# MCU.net
KiCad netlist of a schematic drawn in Altium Designer
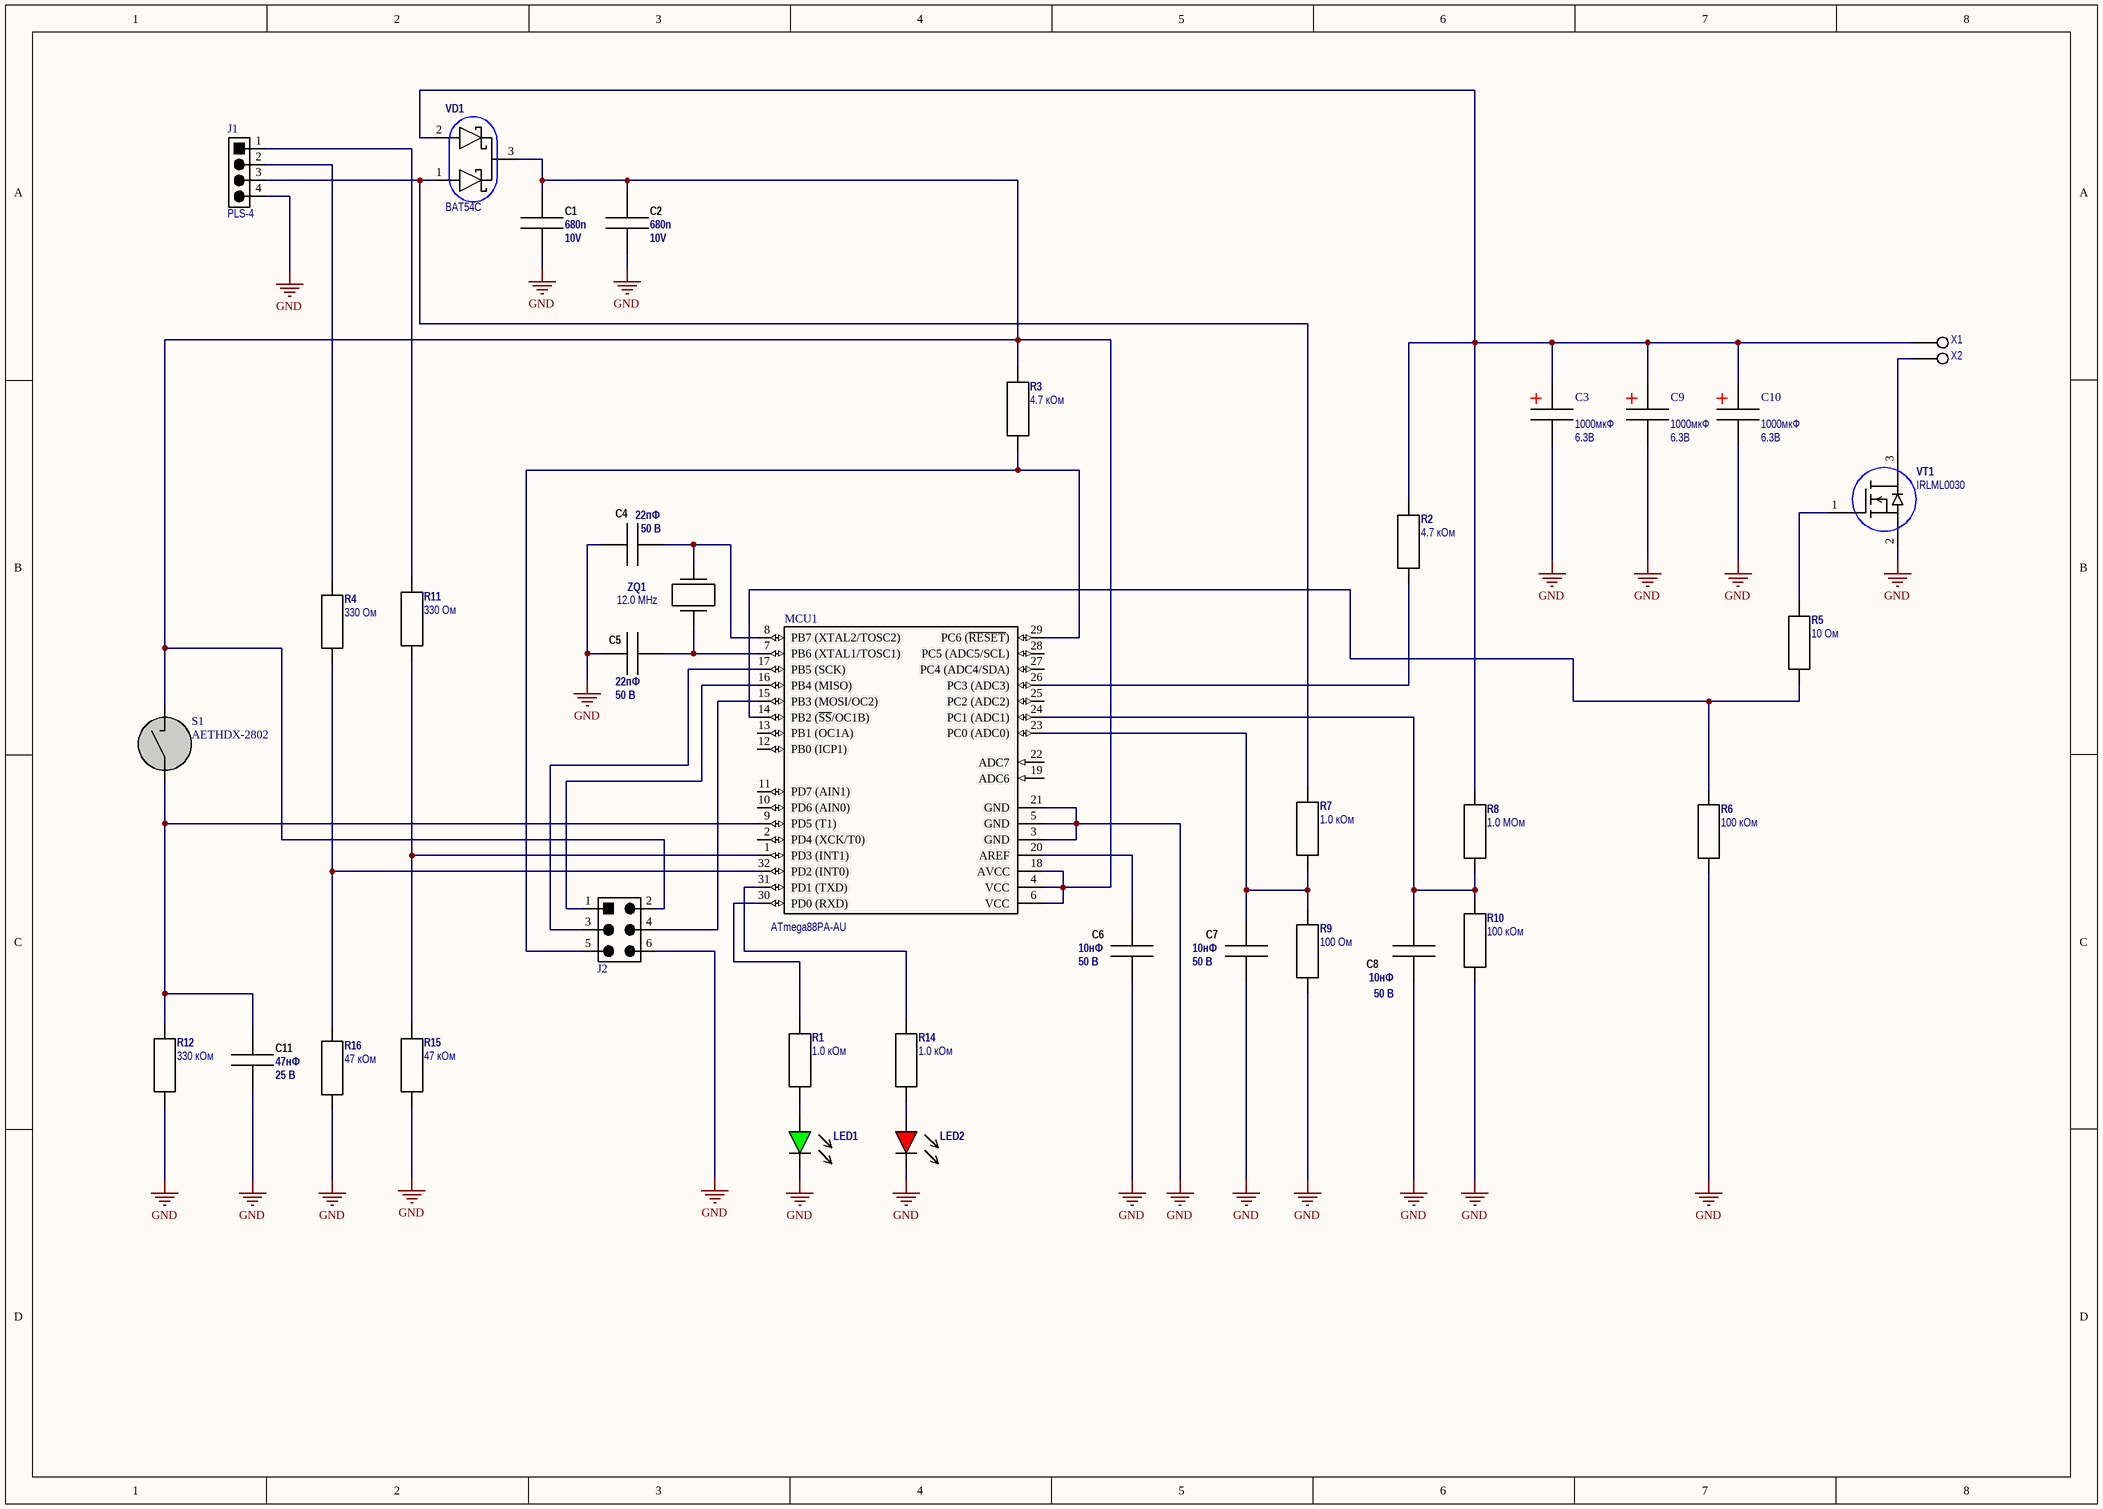
[diagram p0: MCU.SchDoc]

(export (version "E")
  (design (tool "Eeschema 10.0.6"))
  (components
    (comp (ref "C1")
      (value "680нФ 10 В 10% 0603 X7R")
      (footprint "C0603")
      (description "конденсатор керамический SMD")
      (fields
        (field (name "SHOWVALUE") "680n")
        (field (name "VOLTAGE") "10V")
        (field (name "PART NUMBER") "680нФ 10В")
      )
      (libsource (lib "Capacitors 0603 X7R") (part "47нФ 25 В"))
    )
    (comp (ref "C2")
      (value "680нФ 10 В 10% 0603 X7R")
      (footprint "C0603")
      (description "конденсатор керамический SMD")
      (fields
        (field (name "SHOWVALUE") "680n")
        (field (name "VOLTAGE") "10V")
        (field (name "PART NUMBER") "680нФ 10 В")
      )
      (libsource (lib "Capacitors 0603 X7R") (part "47нФ 25 В"))
    )
    (comp (ref "C3")
      (value "1000мкФ")
      (footprint "ELCAP_SMD_8x10.5")
      (description "конденсатор электролитический SMD")
      (fields (field (name "VOLTAGE") "6.3В") (field (name "PART NUMBER") "1000мкФ 6.3В 8x10.5"))
      (libsource (lib "Capacitors Electrolitic SMT") (part "1000мкФ 6.3В 8x10.5"))
    )
    (comp (ref "C4")
      (value "22пФ  5%  50В 0603 NPO")
      (footprint "C0603")
      (description "конденсатор керамический")
      (fields
        (field (name "SHOWVALUE") "22пФ")
        (field (name "VOLTAGE") "50 В")
        (field (name "PART NUMBER") "22пФ  50В")
      )
      (libsource (lib "Capacitors 0603 NPO") (part "22пФ  50В"))
    )
    (comp (ref "C5")
      (value "22пФ  5%  50В 0603 NPO")
      (footprint "C0603")
      (description "конденсатор керамический")
      (fields
        (field (name "SHOWVALUE") "22пФ")
        (field (name "VOLTAGE") "50 В")
        (field (name "PART NUMBER") "22пФ  50В")
      )
      (libsource (lib "Capacitors 0603 NPO") (part "22пФ  50В"))
    )
    (comp (ref "C6")
      (value "10нФ 50 В 10% 0603 X7R")
      (footprint "C0603")
      (description "конденсатор керамический SMD")
      (fields
        (field (name "SHOWVALUE") "10нФ")
        (field (name "VOLTAGE") "50 В")
        (field (name "PART NUMBER") "10нФ 50 В")
      )
      (libsource (lib "Capacitors 0603 X7R") (part "10нФ 50 В"))
    )
    (comp (ref "C7")
      (value "10нФ 50 В 10% 0603 X7R")
      (footprint "C0603")
      (description "конденсатор керамический SMD")
      (fields
        (field (name "SHOWVALUE") "10нФ")
        (field (name "VOLTAGE") "50 В")
        (field (name "PART NUMBER") "10нФ 50 В")
      )
      (libsource (lib "Capacitors 0603 X7R") (part "10нФ 50 В"))
    )
    (comp (ref "C8")
      (value "10нФ 50 В 10% 0603 X7R")
      (footprint "C0603")
      (description "конденсатор керамический SMD")
      (fields
        (field (name "SHOWVALUE") "10нФ")
        (field (name "VOLTAGE") "50 В")
        (field (name "PART NUMBER") "10нФ 50 В")
      )
      (libsource (lib "Capacitors 0603 X7R") (part "10нФ 50 В"))
    )
    (comp (ref "C9")
      (value "1000мкФ")
      (footprint "ELCAP_SMD_8x10.5")
      (description "конденсатор электролитический SMD")
      (fields (field (name "VOLTAGE") "6.3В") (field (name "PART NUMBER") "1000мкФ 6.3В 8x10.5"))
      (libsource (lib "Capacitors Electrolitic SMT") (part "1000мкФ 6.3В 8x10.5"))
    )
    (comp (ref "C10")
      (value "1000мкФ")
      (footprint "ELCAP_SMD_8x10.5")
      (description "конденсатор электролитический SMD")
      (fields (field (name "VOLTAGE") "6.3В") (field (name "PART NUMBER") "1000мкФ 6.3В 8x10.5"))
      (libsource (lib "Capacitors Electrolitic SMT") (part "1000мкФ 6.3В 8x10.5"))
    )
    (comp (ref "C11")
      (value "47нФ 25 В 10% 0603 X7R")
      (footprint "C0603")
      (description "конденсатор керамический SMD")
      (fields
        (field (name "SHOWVALUE") "47нФ")
        (field (name "VOLTAGE") "25 В")
        (field (name "PART NUMBER") "47нФ 25 В")
      )
      (libsource (lib "Capacitors 0603 X7R") (part "47нФ 25 В"))
    )
    (comp (ref "J1")
      (value "PLS-4")
      (footprint "HEADER 1X4")
      (description "Штырьки на плату шаг 2,54 мм")
      (fields (field (name "NAME") "PLS-4"))
      (libsource (lib "Connectors IDC & PLS") (part "PLS-4"))
    )
    (comp (ref "J2")
      (value "PLD-6")
      (footprint "HEADER 2X3")
      (libsource (lib "Connectors IDC & PLS") (part "PLD-6"))
    )
    (comp (ref "LED1")
      (value "~")
      (footprint "LED0805G")
      (description "зеленый светодиод")
      (libsource (lib "LEDs") (part "GB-SM0805UPGW-TR"))
    )
    (comp (ref "LED2")
      (value "~")
      (footprint "LED0805R")
      (description "красный светодиод")
      (libsource (lib "LEDs") (part "GB-SM0805USW-TR"))
    )
    (comp (ref "MCU1")
      (value "ATmega88PA-AU")
      (footprint "LQFP-32-P0.8")
      (fields (field (name "NAME") "ATmega88PA-AU"))
      (libsource (lib "ICs MCU") (part "ATmega8A-AU"))
    )
    (comp (ref "R1")
      (value "1.0 кОм 0603 5%")
      (footprint "R0603")
      (description "резистор постоянный")
      (fields (field (name "SHOWVALUE") "1.0 кОм"))
      (libsource (lib "Resistors 0603 5%") (part "1.0 кОм 0603 5%"))
    )
    (comp (ref "R2")
      (value "4.7 кОм 0603 5%")
      (footprint "R0603")
      (description "резистор постоянный")
      (fields (field (name "SHOWVALUE") "4.7 кОм"))
      (libsource (lib "Resistors 0603 5%") (part "4.7 кОм 0603 5%"))
    )
    (comp (ref "R3")
      (value "4.7 кОм 0603 5%")
      (footprint "R0603")
      (description "резистор постоянный")
      (fields (field (name "SHOWVALUE") "4.7 кОм"))
      (libsource (lib "Resistors 0603 5%") (part "4.7 кОм 0603 5%"))
    )
    (comp (ref "R4")
      (value "330 Ом 0603 5%")
      (footprint "R0603")
      (description "резистор постоянный")
      (fields (field (name "SHOWVALUE") "330 Ом"))
      (libsource (lib "Resistors 0603 5%") (part "330 Ом 0603 5%"))
    )
    (comp (ref "R5")
      (value "10 Ом 0603 5%")
      (footprint "R0603")
      (description "резистор постоянный")
      (fields (field (name "SHOWVALUE") "10 Ом"))
      (libsource (lib "Resistors 0603 5%") (part "10 Ом 0603 5%"))
    )
    (comp (ref "R6")
      (value "100 кОм 0603 5%")
      (footprint "R0603")
      (description "резистор постоянный")
      (fields (field (name "SHOWVALUE") "100 кОм"))
      (libsource (lib "Resistors 0603 5%") (part "100 кОм 0603 5%"))
    )
    (comp (ref "R7")
      (value "1.0 кОм 0603 5%")
      (footprint "R0603")
      (description "резистор постоянный")
      (fields (field (name "SHOWVALUE") "1.0 кОм"))
      (libsource (lib "Resistors 0603 5%") (part "1.0 кОм 0603 5%"))
    )
    (comp (ref "R8")
      (value "1.0 МОм 0603 5%")
      (footprint "R0603")
      (description "резистор постоянный")
      (fields (field (name "SHOWVALUE") "1.0 МОм"))
      (libsource (lib "Resistors 0603 5%") (part "1.0 МОм 0603 5%"))
    )
    (comp (ref "R9")
      (value "100 Ом 0603 5%")
      (footprint "R0603")
      (description "резистор постоянный")
      (fields (field (name "SHOWVALUE") "100 Ом"))
      (libsource (lib "Resistors 0603 5%") (part "100 Ом 0603 5%"))
    )
    (comp (ref "R10")
      (value "100 кОм 0603 5%")
      (footprint "R0603")
      (description "резистор постоянный")
      (fields (field (name "SHOWVALUE") "100 кОм"))
      (libsource (lib "Resistors 0603 5%") (part "100 кОм 0603 5%"))
    )
    (comp (ref "R11")
      (value "330 Ом 0603 5%")
      (footprint "R0603")
      (description "резистор постоянный")
      (fields (field (name "SHOWVALUE") "330 Ом"))
      (libsource (lib "Resistors 0603 5%") (part "330 Ом 0603 5%"))
    )
    (comp (ref "R12")
      (value "330 кОм 0603 5%")
      (footprint "R0603")
      (description "резистор постоянный")
      (fields (field (name "SHOWVALUE") "330 кОм"))
      (libsource (lib "Resistors 0603 5%") (part "330 кОм 0603 5%"))
    )
    (comp (ref "R14")
      (value "1.0 кОм 0603 5%")
      (footprint "R0603")
      (description "резистор постоянный")
      (fields (field (name "SHOWVALUE") "1.0 кОм"))
      (libsource (lib "Resistors 0603 5%") (part "1.0 кОм 0603 5%"))
    )
    (comp (ref "R15")
      (value "47 кОм 0603 5%")
      (footprint "R0603")
      (description "резистор постоянный")
      (fields (field (name "SHOWVALUE") "47 кОм"))
      (libsource (lib "Resistors 0603 5%") (part "47 кОм 0603 5%"))
    )
    (comp (ref "R16")
      (value "47 кОм 0603 5%")
      (footprint "R0603")
      (description "резистор постоянный")
      (fields (field (name "SHOWVALUE") "47 кОм"))
      (libsource (lib "Resistors 0603 5%") (part "47 кОм 0603 5%"))
    )
    (comp (ref "S1")
      (value "AETHDX-2802")
      (footprint "AETHDX-2802")
      (description "Shock sensor AETHDX-2802")
      (libsource (lib "Sensors") (part "AETHDX-2802"))
    )
    (comp (ref "VD1")
      (value "BAT54C")
      (footprint "SOT-23")
      (description "два диода Шоттки")
      (fields (field (name "NAME") "BAT54C"))
      (libsource (lib "Diodes Schottky") (part "BAT54C"))
    )
    (comp (ref "VT1")
      (value "IRLML0030")
      (footprint "SOT-23")
      (description "N-channel MOSFET")
      (fields (field (name "NAME") "IRLML0030"))
      (libsource (lib "Transistors N-Channel") (part "IRLML2060TRPBF"))
    )
    (comp (ref "X1")
      (value "Wire_075")
      (footprint "wire_075")
      (description "Посадочное место под 0,75 кабель")
      (libsource (lib "Механические части") (part "Wire_075"))
    )
    (comp (ref "X2")
      (value "Wire_075")
      (footprint "wire_075")
      (description "Посадочное место под 0,75 кабель")
      (libsource (lib "Механические части") (part "Wire_075"))
    )
    (comp (ref "ZQ1")
      (value "12.0 MHz")
      (footprint "HC-49S")
      (description "Кварцевый резонатор")
      (fields (field (name "Comment") "12.0 MHz HC-49S"))
      (libsource (lib "Cristals") (part "12.0 MHz HC-49S"))
    )
  )
  (nets
    (net (code "1") (name "GND") (class "Default")
      (node (ref "C1") (pin "2") (pinfunction "2_2") (pintype "passive"))
      (node (ref "C10") (pin "2") (pinfunction "2_2") (pintype "passive"))
      (node (ref "C11") (pin "2") (pinfunction "2_2") (pintype "passive"))
      (node (ref "C2") (pin "2") (pinfunction "2_2") (pintype "passive"))
      (node (ref "C3") (pin "2") (pinfunction "2_2") (pintype "passive"))
      (node (ref "C4") (pin "1") (pinfunction "1_1") (pintype "passive"))
      (node (ref "C5") (pin "1") (pinfunction "1_1") (pintype "passive"))
      (node (ref "C6") (pin "2") (pinfunction "2_2") (pintype "passive"))
      (node (ref "C7") (pin "2") (pinfunction "2_2") (pintype "passive"))
      (node (ref "C8") (pin "2") (pinfunction "2_2") (pintype "passive"))
      (node (ref "C9") (pin "2") (pinfunction "2_2") (pintype "passive"))
      (node (ref "J1") (pin "4") (pinfunction "4_4") (pintype "passive"))
      (node (ref "J2") (pin "6") (pinfunction "6_6") (pintype "passive"))
      (node (ref "LED1") (pin "K") (pinfunction "K_K") (pintype "passive"))
      (node (ref "LED2") (pin "K") (pinfunction "K_K") (pintype "passive"))
      (node (ref "MCU1") (pin "21") (pinfunction "GND_21") (pintype "power_in"))
      (node (ref "MCU1") (pin "3") (pinfunction "GND_3") (pintype "power_in"))
      (node (ref "MCU1") (pin "5") (pinfunction "GND_5") (pintype "power_in"))
      (node (ref "R10") (pin "1") (pinfunction "1_1") (pintype "passive"))
      (node (ref "R12") (pin "1") (pinfunction "1_1") (pintype "passive"))
      (node (ref "R15") (pin "1") (pinfunction "1_1") (pintype "passive"))
      (node (ref "R16") (pin "1") (pinfunction "1_1") (pintype "passive"))
      (node (ref "R6") (pin "2") (pinfunction "2_2") (pintype "passive"))
      (node (ref "R9") (pin "1") (pinfunction "1_1") (pintype "passive"))
      (node (ref "VT1") (pin "2") (pinfunction "S_2") (pintype "passive"))
    )
    (net (code "2") (name "Net-(C10-Pad1)") (class "Default")
      (node (ref "C10") (pin "1") (pinfunction "1_1") (pintype "passive"))
      (node (ref "C3") (pin "1") (pinfunction "1_1") (pintype "passive"))
      (node (ref "C9") (pin "1") (pinfunction "1_1") (pintype "passive"))
      (node (ref "R2") (pin "2") (pinfunction "2_2") (pintype "passive"))
      (node (ref "R8") (pin "2") (pinfunction "2_2") (pintype "passive"))
      (node (ref "VD1") (pin "2") (pinfunction "2_2") (pintype "passive"))
      (node (ref "X1") (pin "1") (pinfunction "1_1") (pintype "passive"))
    )
    (net (code "3") (name "Net-(J1-Pad1)") (class "Default")
      (node (ref "J1") (pin "1") (pinfunction "1_1") (pintype "passive"))
      (node (ref "R11") (pin "2") (pinfunction "2_2") (pintype "passive"))
    )
    (net (code "4") (name "Net-(J1-Pad2)") (class "Default")
      (node (ref "J1") (pin "2") (pinfunction "2_2") (pintype "passive"))
      (node (ref "R4") (pin "2") (pinfunction "2_2") (pintype "passive"))
    )
    (net (code "5") (name "Net-(J1-Pad3)") (class "Default")
      (node (ref "J1") (pin "3") (pinfunction "3_3") (pintype "passive"))
      (node (ref "R7") (pin "2") (pinfunction "2_2") (pintype "passive"))
      (node (ref "VD1") (pin "1") (pinfunction "1_1") (pintype "passive"))
    )
    (net (code "6") (name "Net-(LED1-PadA)") (class "Default")
      (node (ref "LED1") (pin "A") (pinfunction "A_A") (pintype "passive"))
      (node (ref "R1") (pin "1") (pinfunction "1_1") (pintype "passive"))
    )
    (net (code "7") (name "Net-(LED2-PadA)") (class "Default")
      (node (ref "LED2") (pin "A") (pinfunction "A_A") (pintype "passive"))
      (node (ref "R14") (pin "1") (pinfunction "1_1") (pintype "passive"))
    )
    (net (code "8") (name "Net-(MCU1-AREF)") (class "Default")
      (node (ref "C6") (pin "1") (pinfunction "1_1") (pintype "passive"))
      (node (ref "MCU1") (pin "20") (pinfunction "AREF_20") (pintype "power_in"))
    )
    (net (code "9") (name "Net-(MCU1-AVCC)") (class "Default")
      (node (ref "C1") (pin "1") (pinfunction "1_1") (pintype "passive"))
      (node (ref "C2") (pin "1") (pinfunction "1_1") (pintype "passive"))
      (node (ref "J2") (pin "2") (pinfunction "2_2") (pintype "passive"))
      (node (ref "MCU1") (pin "18") (pinfunction "AVCC_18") (pintype "power_in"))
      (node (ref "MCU1") (pin "4") (pinfunction "VCC_4") (pintype "power_in"))
      (node (ref "MCU1") (pin "6") (pinfunction "VCC_6") (pintype "power_in"))
      (node (ref "R3") (pin "2") (pinfunction "2_2") (pintype "passive"))
      (node (ref "S1") (pin "1") (pinfunction "1_1") (pintype "passive"))
      (node (ref "VD1") (pin "3") (pinfunction "3_3") (pintype "passive"))
    )
    (net (code "10") (name "Net-(MCU1-PB2_(~{SS}{slash}OC1B))") (class "Default")
      (node (ref "MCU1") (pin "14") (pinfunction "PB2_(~{SS}/OC1B)_14") (pintype "bidirectional"))
      (node (ref "R5") (pin "2") (pinfunction "2_2") (pintype "passive"))
      (node (ref "R6") (pin "1") (pinfunction "1_1") (pintype "passive"))
    )
    (net (code "11") (name "Net-(MCU1-PB3_(MOSI{slash}OC2))") (class "Default")
      (node (ref "J2") (pin "4") (pinfunction "4_4") (pintype "passive"))
      (node (ref "MCU1") (pin "15") (pinfunction "PB3_(MOSI/OC2)_15") (pintype "bidirectional"))
    )
    (net (code "12") (name "Net-(MCU1-PB4_(MISO))") (class "Default")
      (node (ref "J2") (pin "1") (pinfunction "1_1") (pintype "passive"))
      (node (ref "MCU1") (pin "16") (pinfunction "PB4_(MISO)_16") (pintype "bidirectional"))
    )
    (net (code "13") (name "Net-(MCU1-PB5_(SCK))") (class "Default")
      (node (ref "J2") (pin "3") (pinfunction "3_3") (pintype "passive"))
      (node (ref "MCU1") (pin "17") (pinfunction "PB5_(SCK)_17") (pintype "bidirectional"))
    )
    (net (code "14") (name "Net-(MCU1-PB6_(XTAL1{slash}TOSC1))") (class "Default")
      (node (ref "C5") (pin "2") (pinfunction "2_2") (pintype "passive"))
      (node (ref "MCU1") (pin "7") (pinfunction "PB6_(XTAL1/TOSC1)_7") (pintype "bidirectional"))
      (node (ref "ZQ1") (pin "1") (pinfunction "1_1") (pintype "passive"))
    )
    (net (code "15") (name "Net-(MCU1-PB7_(XTAL2{slash}TOSC2))") (class "Default")
      (node (ref "C4") (pin "2") (pinfunction "2_2") (pintype "passive"))
      (node (ref "MCU1") (pin "8") (pinfunction "PB7_(XTAL2/TOSC2)_8") (pintype "bidirectional"))
      (node (ref "ZQ1") (pin "2") (pinfunction "2_2") (pintype "passive"))
    )
    (net (code "16") (name "Net-(MCU1-PC0_(ADC0))") (class "Default")
      (node (ref "C7") (pin "1") (pinfunction "1_1") (pintype "passive"))
      (node (ref "MCU1") (pin "23") (pinfunction "PC0_(ADC0)_23") (pintype "bidirectional"))
      (node (ref "R7") (pin "1") (pinfunction "1_1") (pintype "passive"))
      (node (ref "R9") (pin "2") (pinfunction "2_2") (pintype "passive"))
    )
    (net (code "17") (name "Net-(MCU1-PC1_(ADC1))") (class "Default")
      (node (ref "C8") (pin "1") (pinfunction "1_1") (pintype "passive"))
      (node (ref "MCU1") (pin "24") (pinfunction "PC1_(ADC1)_24") (pintype "bidirectional"))
      (node (ref "R10") (pin "2") (pinfunction "2_2") (pintype "passive"))
      (node (ref "R8") (pin "1") (pinfunction "1_1") (pintype "passive"))
    )
    (net (code "18") (name "Net-(MCU1-PC3_(ADC3))") (class "Default")
      (node (ref "MCU1") (pin "26") (pinfunction "PC3_(ADC3)_26") (pintype "bidirectional"))
      (node (ref "R2") (pin "1") (pinfunction "1_1") (pintype "passive"))
    )
    (net (code "19") (name "Net-(MCU1-PC6_(~{RESET}))") (class "Default")
      (node (ref "J2") (pin "5") (pinfunction "5_5") (pintype "passive"))
      (node (ref "MCU1") (pin "29") (pinfunction "PC6_(~{RESET})_29") (pintype "bidirectional"))
      (node (ref "R3") (pin "1") (pinfunction "1_1") (pintype "passive"))
    )
    (net (code "20") (name "Net-(MCU1-PD0_(RXD))") (class "Default")
      (node (ref "MCU1") (pin "30") (pinfunction "PD0_(RXD)_30") (pintype "bidirectional"))
      (node (ref "R1") (pin "2") (pinfunction "2_2") (pintype "passive"))
    )
    (net (code "21") (name "Net-(MCU1-PD1_(TXD))") (class "Default")
      (node (ref "MCU1") (pin "31") (pinfunction "PD1_(TXD)_31") (pintype "bidirectional"))
      (node (ref "R14") (pin "2") (pinfunction "2_2") (pintype "passive"))
    )
    (net (code "22") (name "Net-(MCU1-PD2_(INT0))") (class "Default")
      (node (ref "MCU1") (pin "32") (pinfunction "PD2_(INT0)_32") (pintype "bidirectional"))
      (node (ref "R16") (pin "2") (pinfunction "2_2") (pintype "passive"))
      (node (ref "R4") (pin "1") (pinfunction "1_1") (pintype "passive"))
    )
    (net (code "23") (name "Net-(MCU1-PD3_(INT1))") (class "Default")
      (node (ref "MCU1") (pin "1") (pinfunction "PD3_(INT1)_1") (pintype "bidirectional"))
      (node (ref "R11") (pin "1") (pinfunction "1_1") (pintype "passive"))
      (node (ref "R15") (pin "2") (pinfunction "2_2") (pintype "passive"))
    )
    (net (code "24") (name "Net-(MCU1-PD5_(T1))") (class "Default")
      (node (ref "C11") (pin "1") (pinfunction "1_1") (pintype "passive"))
      (node (ref "MCU1") (pin "9") (pinfunction "PD5_(T1)_9") (pintype "bidirectional"))
      (node (ref "R12") (pin "2") (pinfunction "2_2") (pintype "passive"))
      (node (ref "S1") (pin "0") (pinfunction "0_0") (pintype "passive"))
    )
    (net (code "25") (name "Net-(VT1-D)") (class "Default")
      (node (ref "VT1") (pin "3") (pinfunction "D_3") (pintype "passive"))
      (node (ref "X2") (pin "1") (pinfunction "1_1") (pintype "passive"))
    )
    (net (code "26") (name "Net-(VT1-G)") (class "Default")
      (node (ref "R5") (pin "1") (pinfunction "1_1") (pintype "passive"))
      (node (ref "VT1") (pin "1") (pinfunction "G_1") (pintype "passive"))
    )
    (net (code "27") (name "unconnected-(MCU1-ADC6-Pad19)") (class "Default")
      (node (ref "MCU1") (pin "19") (pinfunction "ADC6_19") (pintype "input"))
    )
    (net (code "28") (name "unconnected-(MCU1-ADC7-Pad22)") (class "Default")
      (node (ref "MCU1") (pin "22") (pinfunction "ADC7_22") (pintype "input"))
    )
    (net (code "29") (name "unconnected-(MCU1-PB0_(ICP1)-Pad12)") (class "Default")
      (node (ref "MCU1") (pin "12") (pinfunction "PB0_(ICP1)_12") (pintype "bidirectional"))
    )
    (net (code "30") (name "unconnected-(MCU1-PB1_(OC1A)-Pad13)") (class "Default")
      (node (ref "MCU1") (pin "13") (pinfunction "PB1_(OC1A)_13") (pintype "bidirectional"))
    )
    (net (code "31") (name "unconnected-(MCU1-PC2_(ADC2)-Pad25)") (class "Default")
      (node (ref "MCU1") (pin "25") (pinfunction "PC2_(ADC2)_25") (pintype "bidirectional"))
    )
    (net (code "32") (name "unconnected-(MCU1-PC4_(ADC4{slash}SDA)-Pad27)") (class "Default")
      (node (ref "MCU1") (pin "27") (pinfunction "PC4_(ADC4/SDA)_27") (pintype "bidirectional"))
    )
    (net (code "33") (name "unconnected-(MCU1-PC5_(ADC5{slash}SCL)-Pad28)") (class "Default")
      (node (ref "MCU1") (pin "28") (pinfunction "PC5_(ADC5/SCL)_28") (pintype "bidirectional"))
    )
    (net (code "34") (name "unconnected-(MCU1-PD4_(XCK{slash}T0)-Pad2)") (class "Default")
      (node (ref "MCU1") (pin "2") (pinfunction "PD4_(XCK/T0)_2") (pintype "bidirectional"))
    )
    (net (code "35") (name "unconnected-(MCU1-PD6_(AIN0)-Pad10)") (class "Default")
      (node (ref "MCU1") (pin "10") (pinfunction "PD6_(AIN0)_10") (pintype "bidirectional"))
    )
    (net (code "36") (name "unconnected-(MCU1-PD7_(AIN1)-Pad11)") (class "Default")
      (node (ref "MCU1") (pin "11") (pinfunction "PD7_(AIN1)_11") (pintype "bidirectional"))
    )
  )
)
